# PRZYSTAWKA_230_-_ILUMINOFONIA.net
KiCad netlist of a schematic drawn in EAGLE
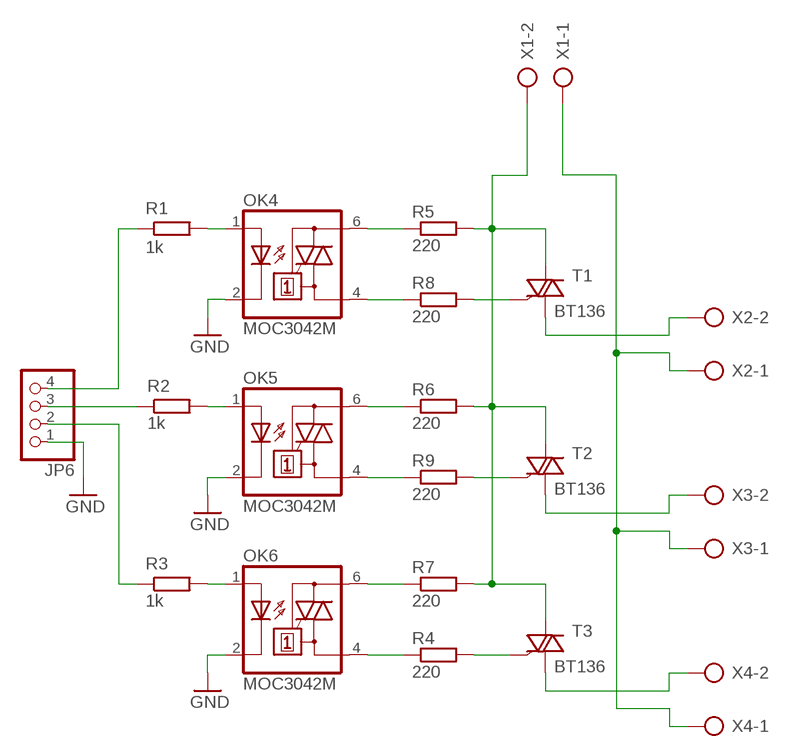
[diagram p0: schematic, sheet 1]

(export (version "E")
  (design (tool "Eeschema 10.0.6"))
  (components
    (comp (ref "JP6")
      (value "PINHD-1X4")
      (footprint "eagle-import:1X04")
      (libsource (lib "eagle-import") (part "PINHD-1X4"))
    )
    (comp (ref "OK4")
      (value "MOC3042M")
      (footprint "eagle-import:DIL06")
      (fields (field (name "MF") "FAIRCHILD SEMICONDUCTOR") (field (name "MPN") "MOC3042-M"))
      (libsource (lib "eagle-import") (part "MOC3042M"))
    )
    (comp (ref "OK5")
      (value "MOC3042M")
      (footprint "eagle-import:DIL06")
      (fields (field (name "MF") "FAIRCHILD SEMICONDUCTOR") (field (name "MPN") "MOC3042-M"))
      (libsource (lib "eagle-import") (part "MOC3042M"))
    )
    (comp (ref "OK6")
      (value "MOC3042M")
      (footprint "eagle-import:DIL06")
      (fields (field (name "MF") "FAIRCHILD SEMICONDUCTOR") (field (name "MPN") "MOC3042-M"))
      (libsource (lib "eagle-import") (part "MOC3042M"))
    )
    (comp (ref "R1")
      (value "1k")
      (footprint "eagle-import:204_5")
      (libsource (lib "eagle-import") (part "R_EU"))
    )
    (comp (ref "R2")
      (value "1k")
      (footprint "eagle-import:204_5")
      (libsource (lib "eagle-import") (part "R_EU"))
    )
    (comp (ref "R3")
      (value "1k")
      (footprint "eagle-import:204_5")
      (libsource (lib "eagle-import") (part "R_EU"))
    )
    (comp (ref "R4")
      (value "220")
      (footprint "eagle-import:204_5")
      (libsource (lib "eagle-import") (part "R_EU"))
    )
    (comp (ref "R5")
      (value "220")
      (footprint "eagle-import:204_5")
      (libsource (lib "eagle-import") (part "R_EU"))
    )
    (comp (ref "R6")
      (value "220")
      (footprint "eagle-import:204_5")
      (libsource (lib "eagle-import") (part "R_EU"))
    )
    (comp (ref "R7")
      (value "220")
      (footprint "eagle-import:204_5")
      (libsource (lib "eagle-import") (part "R_EU"))
    )
    (comp (ref "R8")
      (value "220")
      (footprint "eagle-import:204_5")
      (libsource (lib "eagle-import") (part "R_EU"))
    )
    (comp (ref "R9")
      (value "220")
      (footprint "eagle-import:204_5")
      (libsource (lib "eagle-import") (part "R_EU"))
    )
    (comp (ref "T1")
      (value "BT136")
      (footprint "eagle-import:TO220AB")
      (libsource (lib "eagle-import") (part "BT136"))
    )
    (comp (ref "T2")
      (value "BT136")
      (footprint "eagle-import:TO220AB")
      (libsource (lib "eagle-import") (part "BT136"))
    )
    (comp (ref "T3")
      (value "BT136")
      (footprint "eagle-import:TO220AB")
      (libsource (lib "eagle-import") (part "BT136"))
    )
    (comp (ref "X1")
      (value "AK300/2")
      (footprint "eagle-import:AK300_2")
      (libsource (lib "eagle-import") (part "AK300/2"))
    )
    (comp (ref "X2")
      (value "AK300/2")
      (footprint "eagle-import:AK300_2")
      (libsource (lib "eagle-import") (part "AK300/2"))
    )
    (comp (ref "X3")
      (value "AK300/2")
      (footprint "eagle-import:AK300_2")
      (libsource (lib "eagle-import") (part "AK300/2"))
    )
    (comp (ref "X4")
      (value "AK300/2")
      (footprint "eagle-import:AK300_2")
      (libsource (lib "eagle-import") (part "AK300/2"))
    )
  )
  (nets
    (net (code "1") (name "GND") (class "Default")
      (node (ref "JP6") (pin "1") (pinfunction "1_1") (pintype "passive"))
      (node (ref "OK4") (pin "2") (pinfunction "C_2") (pintype "passive"))
      (node (ref "OK5") (pin "2") (pinfunction "C_2") (pintype "passive"))
      (node (ref "OK6") (pin "2") (pinfunction "C_2") (pintype "passive"))
    )
    (net (code "2") (name "Net-(OK4-A)") (class "Default")
      (node (ref "OK4") (pin "1") (pinfunction "A_1") (pintype "passive"))
      (node (ref "R1") (pin "P$2") (pinfunction "2_P$2") (pintype "passive"))
    )
    (net (code "3") (name "Net-(OK4-A1)") (class "Default")
      (node (ref "OK4") (pin "4") (pinfunction "A1_4") (pintype "passive"))
      (node (ref "R8") (pin "P$1") (pinfunction "1_P$1") (pintype "passive"))
    )
    (net (code "4") (name "Net-(OK4-A2)") (class "Default")
      (node (ref "OK4") (pin "6") (pinfunction "A2_6") (pintype "passive"))
      (node (ref "R5") (pin "P$1") (pinfunction "1_P$1") (pintype "passive"))
    )
    (net (code "5") (name "Net-(OK5-A)") (class "Default")
      (node (ref "OK5") (pin "1") (pinfunction "A_1") (pintype "passive"))
      (node (ref "R2") (pin "P$2") (pinfunction "2_P$2") (pintype "passive"))
    )
    (net (code "6") (name "Net-(OK5-A1)") (class "Default")
      (node (ref "OK5") (pin "4") (pinfunction "A1_4") (pintype "passive"))
      (node (ref "R9") (pin "P$1") (pinfunction "1_P$1") (pintype "passive"))
    )
    (net (code "7") (name "Net-(OK5-A2)") (class "Default")
      (node (ref "OK5") (pin "6") (pinfunction "A2_6") (pintype "passive"))
      (node (ref "R6") (pin "P$1") (pinfunction "1_P$1") (pintype "passive"))
    )
    (net (code "8") (name "Net-(OK6-A)") (class "Default")
      (node (ref "OK6") (pin "1") (pinfunction "A_1") (pintype "passive"))
      (node (ref "R3") (pin "P$2") (pinfunction "2_P$2") (pintype "passive"))
    )
    (net (code "9") (name "Net-(OK6-A1)") (class "Default")
      (node (ref "OK6") (pin "4") (pinfunction "A1_4") (pintype "passive"))
      (node (ref "R4") (pin "P$1") (pinfunction "1_P$1") (pintype "passive"))
    )
    (net (code "10") (name "Net-(OK6-A2)") (class "Default")
      (node (ref "OK6") (pin "6") (pinfunction "A2_6") (pintype "passive"))
      (node (ref "R7") (pin "P$1") (pinfunction "1_P$1") (pintype "passive"))
    )
    (net (code "11") (name "Net-(R1-1)") (class "Default")
      (node (ref "JP6") (pin "4") (pinfunction "4_4") (pintype "passive"))
      (node (ref "R1") (pin "P$1") (pinfunction "1_P$1") (pintype "passive"))
    )
    (net (code "12") (name "Net-(R2-1)") (class "Default")
      (node (ref "JP6") (pin "3") (pinfunction "3_3") (pintype "passive"))
      (node (ref "R2") (pin "P$1") (pinfunction "1_P$1") (pintype "passive"))
    )
    (net (code "13") (name "Net-(R3-1)") (class "Default")
      (node (ref "JP6") (pin "2") (pinfunction "2_2") (pintype "passive"))
      (node (ref "R3") (pin "P$1") (pinfunction "1_P$1") (pintype "passive"))
    )
    (net (code "14") (name "Net-(R4-2)") (class "Default")
      (node (ref "R4") (pin "P$2") (pinfunction "2_P$2") (pintype "passive"))
      (node (ref "T3") (pin "3") (pinfunction "G_3") (pintype "passive"))
    )
    (net (code "15") (name "Net-(R5-2)") (class "Default")
      (node (ref "R5") (pin "P$2") (pinfunction "2_P$2") (pintype "passive"))
      (node (ref "R6") (pin "P$2") (pinfunction "2_P$2") (pintype "passive"))
      (node (ref "R7") (pin "P$2") (pinfunction "2_P$2") (pintype "passive"))
      (node (ref "T1") (pin "2") (pinfunction "A2_2") (pintype "passive"))
      (node (ref "T2") (pin "2") (pinfunction "A2_2") (pintype "passive"))
      (node (ref "T3") (pin "2") (pinfunction "A2_2") (pintype "passive"))
      (node (ref "X1") (pin "2") (pinfunction "KL_2") (pintype "passive"))
    )
    (net (code "16") (name "Net-(R8-2)") (class "Default")
      (node (ref "R8") (pin "P$2") (pinfunction "2_P$2") (pintype "passive"))
      (node (ref "T1") (pin "3") (pinfunction "G_3") (pintype "passive"))
    )
    (net (code "17") (name "Net-(R9-2)") (class "Default")
      (node (ref "R9") (pin "P$2") (pinfunction "2_P$2") (pintype "passive"))
      (node (ref "T2") (pin "3") (pinfunction "G_3") (pintype "passive"))
    )
    (net (code "18") (name "Net-(T1-A1)") (class "Default")
      (node (ref "T1") (pin "1") (pinfunction "A1_1") (pintype "passive"))
      (node (ref "X2") (pin "2") (pinfunction "KL_2") (pintype "passive"))
    )
    (net (code "19") (name "Net-(T2-A1)") (class "Default")
      (node (ref "T2") (pin "1") (pinfunction "A1_1") (pintype "passive"))
      (node (ref "X3") (pin "2") (pinfunction "KL_2") (pintype "passive"))
    )
    (net (code "20") (name "Net-(T3-A1)") (class "Default")
      (node (ref "T3") (pin "1") (pinfunction "A1_1") (pintype "passive"))
      (node (ref "X4") (pin "2") (pinfunction "KL_2") (pintype "passive"))
    )
    (net (code "21") (name "Net-(X1A-KL)") (class "Default")
      (node (ref "X1") (pin "1") (pinfunction "KL_1") (pintype "passive"))
      (node (ref "X2") (pin "1") (pinfunction "KL_1") (pintype "passive"))
      (node (ref "X3") (pin "1") (pinfunction "KL_1") (pintype "passive"))
      (node (ref "X4") (pin "1") (pinfunction "KL_1") (pintype "passive"))
    )
  )
)
